# sc_v1.net
KiCad netlist of a schematic drawn in EAGLE
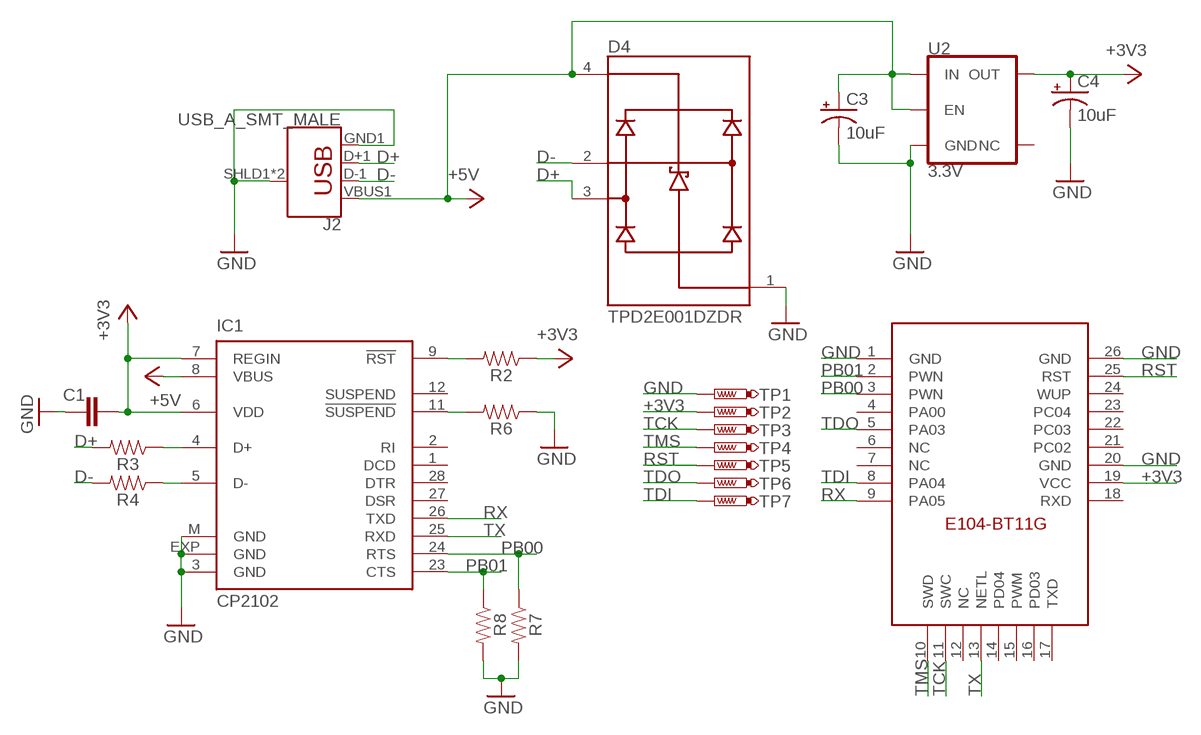
[diagram p0: schematic, sheet 1]

(export (version "E")
  (design (tool "Eeschema 10.0.6"))
  (components
    (comp (ref "C1")
      (value "100nf")
      (footprint "eagle-import:CAPC1005X40N")
      (fields (field (name "MF") "Yageo") (field (name "MP") "RC0402FR-073M6L"))
      (libsource (lib "eagle-import") (part "CAP0402"))
    )
    (comp (ref "C3")
      (value "10uF")
      (footprint "eagle-import:0603-POLAR")
      (libsource (lib "eagle-import") (part "10UF-POLAR-0603-6.3V-20%(TANT)"))
    )
    (comp (ref "C4")
      (value "10uF")
      (footprint "eagle-import:0603-POLAR")
      (libsource (lib "eagle-import") (part "10UF-POLAR-0603-6.3V-20%(TANT)"))
    )
    (comp (ref "D4")
      (value "TPD2E001DZDR")
      (footprint "eagle-import:SOT192P237X122-4N")
      (fields (field (name "MF") "Texas Instruments"))
      (libsource (lib "eagle-import") (part "TPD2E001DZDR"))
    )
    (comp (ref "IC1")
      (value "CP2102")
      (footprint "eagle-import:MLP28")
      (fields (field (name "MF") "FARNELL") (field (name "MPN") "CP2102-GM"))
      (libsource (lib "eagle-import") (part "CP2102"))
    )
    (comp (ref "J2")
      (value "USB_A_SMT_MALE")
      (footprint "eagle-import:USB-A-SMT-MALE")
      (libsource (lib "eagle-import") (part "USB_A_SMT_MALE"))
    )
    (comp (ref "R2")
      (value "4.7k")
      (footprint "eagle-import:0402")
      (libsource (lib "eagle-import") (part "RESISTOR0402"))
    )
    (comp (ref "R3")
      (value "30Ohm")
      (footprint "eagle-import:0402")
      (libsource (lib "eagle-import") (part "RESISTOR0402"))
    )
    (comp (ref "R4")
      (value "30Ohm")
      (footprint "eagle-import:0402")
      (libsource (lib "eagle-import") (part "RESISTOR0402"))
    )
    (comp (ref "R6")
      (value "10k")
      (footprint "eagle-import:0402")
      (libsource (lib "eagle-import") (part "RESISTOR0402"))
    )
    (comp (ref "R7")
      (value "10k")
      (footprint "eagle-import:0402")
      (libsource (lib "eagle-import") (part "RESISTOR0402"))
    )
    (comp (ref "R8")
      (value "10k")
      (footprint "eagle-import:0402")
      (libsource (lib "eagle-import") (part "RESISTOR0402"))
    )
    (comp (ref "TP1")
      (value "PTR1TP10R")
      (footprint "eagle-import:TP10R")
      (libsource (lib "eagle-import") (part "PTR1TP10R"))
    )
    (comp (ref "TP2")
      (value "PTR1TP10R")
      (footprint "eagle-import:TP10R")
      (libsource (lib "eagle-import") (part "PTR1TP10R"))
    )
    (comp (ref "TP3")
      (value "PTR1TP10R")
      (footprint "eagle-import:TP10R")
      (libsource (lib "eagle-import") (part "PTR1TP10R"))
    )
    (comp (ref "TP4")
      (value "PTR1TP10R")
      (footprint "eagle-import:TP10R")
      (libsource (lib "eagle-import") (part "PTR1TP10R"))
    )
    (comp (ref "TP5")
      (value "PTR1TP10R")
      (footprint "eagle-import:TP10R")
      (libsource (lib "eagle-import") (part "PTR1TP10R"))
    )
    (comp (ref "TP6")
      (value "PTR1TP10R")
      (footprint "eagle-import:TP10R")
      (libsource (lib "eagle-import") (part "PTR1TP10R"))
    )
    (comp (ref "TP7")
      (value "PTR1TP10R")
      (footprint "eagle-import:TP10R")
      (libsource (lib "eagle-import") (part "PTR1TP10R"))
    )
    (comp (ref "U$1")
      (value "E104-BT11G-PCBPCB")
      (footprint "eagle-import:E104-BT11G-PCB")
      (libsource (lib "eagle-import") (part "E104-BT11G-PCBPCB"))
    )
    (comp (ref "U2")
      (value "3.3V")
      (footprint "eagle-import:SOT23-5")
      (libsource (lib "eagle-import") (part "V_REG_AP2112K-3.3V"))
    )
  )
  (nets
    (net (code "1") (name "+3V3") (class "Default")
      (node (ref "C1") (pin "2") (pinfunction "2_2") (pintype "passive"))
      (node (ref "C4") (pin "+") (pinfunction "+_+") (pintype "passive"))
      (node (ref "IC1") (pin "6") (pinfunction "VDD_6") (pintype "power_in"))
      (node (ref "IC1") (pin "7") (pinfunction "REGIN_7") (pintype "passive"))
      (node (ref "R2") (pin "1") (pinfunction "1_1") (pintype "passive"))
      (node (ref "TP2") (pin "TP") (pinfunction "TP_TP") (pintype "input"))
      (node (ref "U$1") (pin "19") (pinfunction "VCC_19") (pintype "bidirectional"))
      (node (ref "U2") (pin "5") (pinfunction "OUT_5") (pintype "passive"))
    )
    (net (code "2") (name "+5V") (class "Default")
      (node (ref "C3") (pin "+") (pinfunction "+_+") (pintype "passive"))
      (node (ref "D4") (pin "4") (pinfunction "VCC_4") (pintype "power_in"))
      (node (ref "IC1") (pin "8") (pinfunction "VBUS_8") (pintype "input"))
      (node (ref "J2") (pin "VBUS1") (pinfunction "VBUS_VBUS1") (pintype "power_in"))
      (node (ref "U2") (pin "1") (pinfunction "IN_1") (pintype "input"))
      (node (ref "U2") (pin "3") (pinfunction "EN_3") (pintype "input"))
    )
    (net (code "3") (name "/D+") (class "Default")
      (node (ref "D4") (pin "3") (pinfunction "IO2_3") (pintype "bidirectional"))
      (node (ref "J2") (pin "D+1") (pinfunction "D+_D+1") (pintype "bidirectional"))
      (node (ref "R3") (pin "2") (pinfunction "2_2") (pintype "passive"))
    )
    (net (code "4") (name "/D-") (class "Default")
      (node (ref "D4") (pin "2") (pinfunction "IO1_2") (pintype "bidirectional"))
      (node (ref "J2") (pin "D-1") (pinfunction "D-_D-1") (pintype "bidirectional"))
      (node (ref "R4") (pin "2") (pinfunction "2_2") (pintype "passive"))
    )
    (net (code "5") (name "/PB00") (class "Default")
      (node (ref "IC1") (pin "24") (pinfunction "RTS_24") (pintype "output"))
      (node (ref "R7") (pin "1") (pinfunction "1_1") (pintype "passive"))
      (node (ref "U$1") (pin "3") (pinfunction "PWN_3") (pintype "bidirectional"))
    )
    (net (code "6") (name "/PB01") (class "Default")
      (node (ref "IC1") (pin "23") (pinfunction "CTS_23") (pintype "input"))
      (node (ref "R8") (pin "1") (pinfunction "1_1") (pintype "passive"))
      (node (ref "U$1") (pin "2") (pinfunction "PWN_2") (pintype "bidirectional"))
    )
    (net (code "7") (name "/RST") (class "Default")
      (node (ref "TP5") (pin "TP") (pinfunction "TP_TP") (pintype "input"))
      (node (ref "U$1") (pin "25") (pinfunction "RST_25") (pintype "bidirectional"))
    )
    (net (code "8") (name "/RX") (class "Default")
      (node (ref "IC1") (pin "26") (pinfunction "TXD_26") (pintype "output"))
      (node (ref "U$1") (pin "9") (pinfunction "PA05_9") (pintype "bidirectional"))
    )
    (net (code "9") (name "/TCK") (class "Default")
      (node (ref "TP3") (pin "TP") (pinfunction "TP_TP") (pintype "input"))
      (node (ref "U$1") (pin "11") (pinfunction "SWC_11") (pintype "bidirectional"))
    )
    (net (code "10") (name "/TDI") (class "Default")
      (node (ref "TP7") (pin "TP") (pinfunction "TP_TP") (pintype "input"))
      (node (ref "U$1") (pin "8") (pinfunction "PA04_8") (pintype "bidirectional"))
    )
    (net (code "11") (name "/TDO") (class "Default")
      (node (ref "TP6") (pin "TP") (pinfunction "TP_TP") (pintype "input"))
      (node (ref "U$1") (pin "5") (pinfunction "PA03_5") (pintype "bidirectional"))
    )
    (net (code "12") (name "/TMS") (class "Default")
      (node (ref "TP4") (pin "TP") (pinfunction "TP_TP") (pintype "input"))
      (node (ref "U$1") (pin "10") (pinfunction "SWD_10") (pintype "bidirectional"))
    )
    (net (code "13") (name "/TX") (class "Default")
      (node (ref "IC1") (pin "25") (pinfunction "RXD_25") (pintype "input"))
      (node (ref "U$1") (pin "13") (pinfunction "NETL_13") (pintype "bidirectional"))
    )
    (net (code "14") (name "GND") (class "Default")
      (node (ref "C1") (pin "1") (pinfunction "1_1") (pintype "passive"))
      (node (ref "C3") (pin "-") (pinfunction "-_-") (pintype "passive"))
      (node (ref "C4") (pin "-") (pinfunction "-_-") (pintype "passive"))
      (node (ref "D4") (pin "1") (pinfunction "GND_1") (pintype "power_in"))
      (node (ref "IC1") (pin "3") (pinfunction "GND_3") (pintype "power_in"))
      (node (ref "IC1") (pin "EXP") (pinfunction "GND_EXP") (pintype "power_in"))
      (node (ref "IC1") (pin "M") (pinfunction "GND_M") (pintype "power_in"))
      (node (ref "J2") (pin "GND1") (pinfunction "GND_GND1") (pintype "power_in"))
      (node (ref "J2") (pin "SHLD1") (pinfunction "SHIELD_SHLD1") (pintype "bidirectional"))
      (node (ref "J2") (pin "SHLD2") (pinfunction "SHIELD_SHLD2") (pintype "bidirectional"))
      (node (ref "R6") (pin "1") (pinfunction "1_1") (pintype "passive"))
      (node (ref "R7") (pin "2") (pinfunction "2_2") (pintype "passive"))
      (node (ref "R8") (pin "2") (pinfunction "2_2") (pintype "passive"))
      (node (ref "TP1") (pin "TP") (pinfunction "TP_TP") (pintype "input"))
      (node (ref "U$1") (pin "1") (pinfunction "GND_1") (pintype "bidirectional"))
      (node (ref "U$1") (pin "20") (pinfunction "GND_20") (pintype "bidirectional"))
      (node (ref "U$1") (pin "26") (pinfunction "GND_26") (pintype "bidirectional"))
      (node (ref "U2") (pin "2") (pinfunction "GND_2") (pintype "input"))
    )
    (net (code "15") (name "Net-(IC1-D+)") (class "Default")
      (node (ref "IC1") (pin "4") (pinfunction "D+_4") (pintype "bidirectional"))
      (node (ref "R3") (pin "1") (pinfunction "1_1") (pintype "passive"))
    )
    (net (code "16") (name "Net-(IC1-D-)") (class "Default")
      (node (ref "IC1") (pin "5") (pinfunction "D-_5") (pintype "bidirectional"))
      (node (ref "R4") (pin "1") (pinfunction "1_1") (pintype "passive"))
    )
    (net (code "17") (name "Net-(IC1-~{RST})") (class "Default")
      (node (ref "IC1") (pin "9") (pinfunction "~{RST}_9") (pintype "bidirectional"))
      (node (ref "R2") (pin "2") (pinfunction "2_2") (pintype "passive"))
    )
    (net (code "18") (name "Net-(IC1-~{SUSPEND})") (class "Default")
      (node (ref "IC1") (pin "11") (pinfunction "~{SUSPEND}_11") (pintype "output"))
      (node (ref "R6") (pin "2") (pinfunction "2_2") (pintype "passive"))
    )
    (net (code "19") (name "unconnected-(IC1-DCD-Pad1)") (class "Default")
      (node (ref "IC1") (pin "1") (pinfunction "DCD_1") (pintype "input"))
    )
    (net (code "20") (name "unconnected-(IC1-DSR-Pad27)") (class "Default")
      (node (ref "IC1") (pin "27") (pinfunction "DSR_27") (pintype "input"))
    )
    (net (code "21") (name "unconnected-(IC1-DTR-Pad28)") (class "Default")
      (node (ref "IC1") (pin "28") (pinfunction "DTR_28") (pintype "output"))
    )
    (net (code "22") (name "unconnected-(IC1-RI-Pad2)") (class "Default")
      (node (ref "IC1") (pin "2") (pinfunction "RI_2") (pintype "input"))
    )
    (net (code "23") (name "unconnected-(IC1-SUSPEND-Pad12)") (class "Default")
      (node (ref "IC1") (pin "12") (pinfunction "SUSPEND_12") (pintype "output"))
    )
    (net (code "24") (name "unconnected-(U$1-NC-Pad6)") (class "Default")
      (node (ref "U$1") (pin "6") (pinfunction "NC_6") (pintype "bidirectional"))
    )
    (net (code "25") (name "unconnected-(U$1-NC-Pad7)") (class "Default")
      (node (ref "U$1") (pin "7") (pinfunction "NC_7") (pintype "bidirectional"))
    )
    (net (code "26") (name "unconnected-(U$1-NC-Pad12)") (class "Default")
      (node (ref "U$1") (pin "12") (pinfunction "NC_12") (pintype "bidirectional"))
    )
    (net (code "27") (name "unconnected-(U$1-PA00-Pad4)") (class "Default")
      (node (ref "U$1") (pin "4") (pinfunction "PA00_4") (pintype "bidirectional"))
    )
    (net (code "28") (name "unconnected-(U$1-PC02-Pad21)") (class "Default")
      (node (ref "U$1") (pin "21") (pinfunction "PC02_21") (pintype "bidirectional"))
    )
    (net (code "29") (name "unconnected-(U$1-PC03-Pad22)") (class "Default")
      (node (ref "U$1") (pin "22") (pinfunction "PC03_22") (pintype "bidirectional"))
    )
    (net (code "30") (name "unconnected-(U$1-PC04-Pad23)") (class "Default")
      (node (ref "U$1") (pin "23") (pinfunction "PC04_23") (pintype "bidirectional"))
    )
    (net (code "31") (name "unconnected-(U$1-PD03-Pad16)") (class "Default")
      (node (ref "U$1") (pin "16") (pinfunction "PD03_16") (pintype "bidirectional"))
    )
    (net (code "32") (name "unconnected-(U$1-PD04-Pad14)") (class "Default")
      (node (ref "U$1") (pin "14") (pinfunction "PD04_14") (pintype "bidirectional"))
    )
    (net (code "33") (name "unconnected-(U$1-PWM-Pad15)") (class "Default")
      (node (ref "U$1") (pin "15") (pinfunction "PWM_15") (pintype "bidirectional"))
    )
    (net (code "34") (name "unconnected-(U$1-RXD-Pad18)") (class "Default")
      (node (ref "U$1") (pin "18") (pinfunction "RXD_18") (pintype "bidirectional"))
    )
    (net (code "35") (name "unconnected-(U$1-TXD-Pad17)") (class "Default")
      (node (ref "U$1") (pin "17") (pinfunction "TXD_17") (pintype "bidirectional"))
    )
    (net (code "36") (name "unconnected-(U$1-WUP-Pad24)") (class "Default")
      (node (ref "U$1") (pin "24") (pinfunction "WUP_24") (pintype "bidirectional"))
    )
    (net (code "37") (name "unconnected-(U2-NC-Pad4)") (class "Default")
      (node (ref "U2") (pin "4") (pinfunction "NC_4") (pintype "no_connect"))
    )
  )
)
